# oldSHSDHDTD_system_1.net
KiCad netlist of a schematic drawn in EAGLE
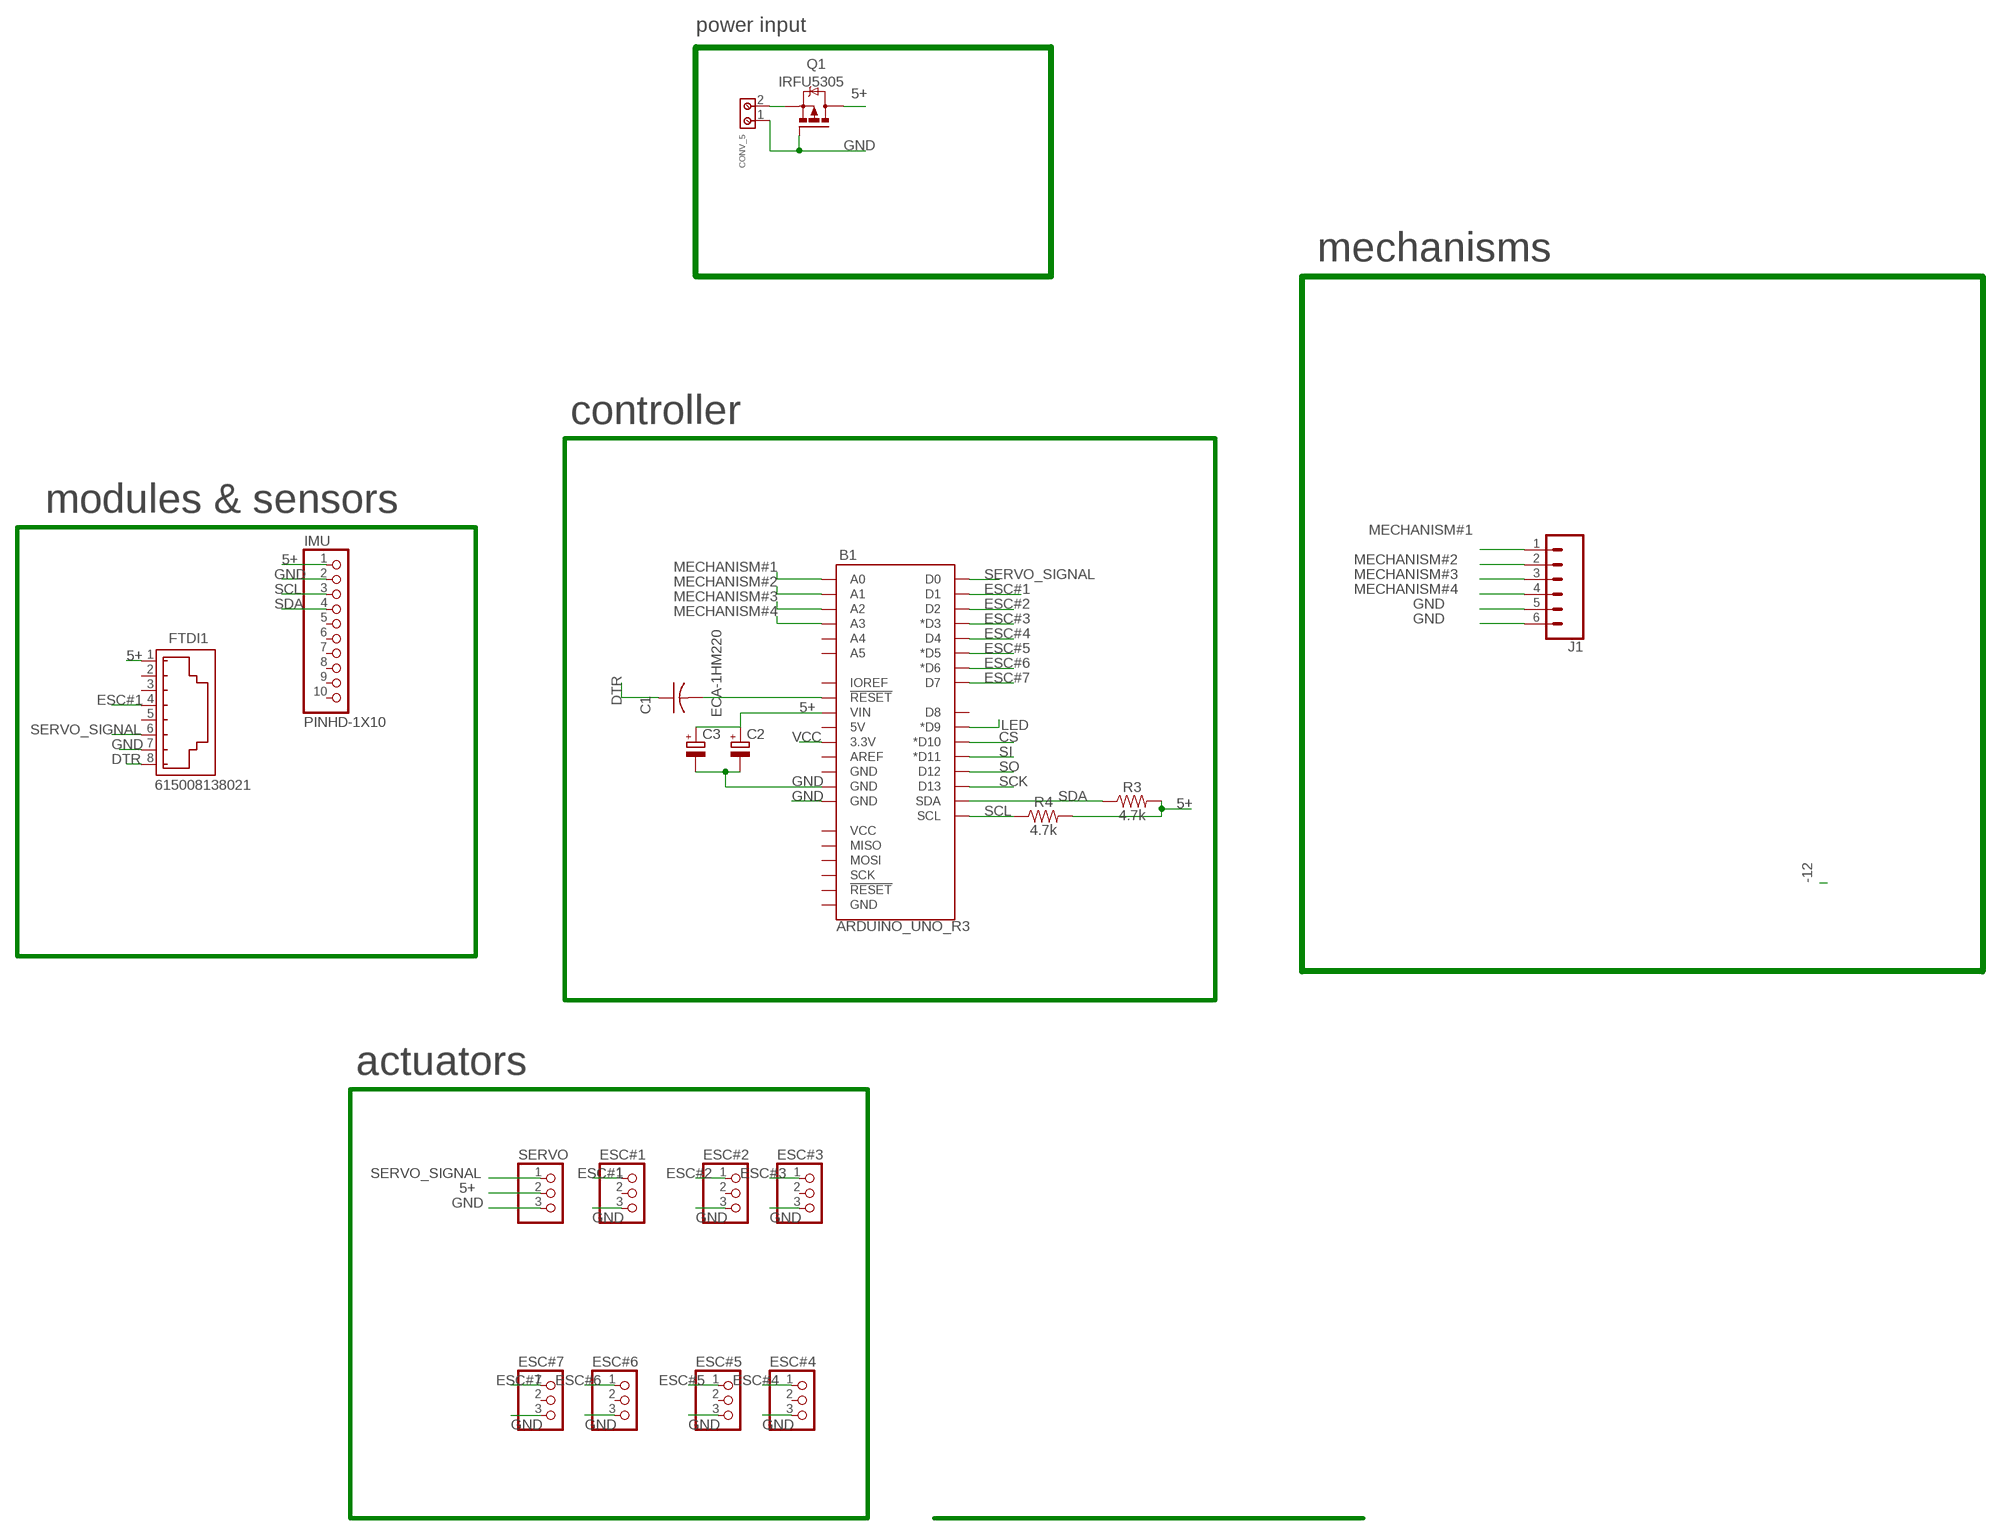
[diagram p0: schematic, sheet 1]

(export (version "E")
  (design (tool "Eeschema 10.0.6"))
  (components
    (comp (ref "B1")
      (value "ARDUINO_UNO_R3")
      (footprint "eagle-import:ARDUINO_R3")
      (libsource (lib "eagle-import") (part "ARDUINO_UNO_R3"))
    )
    (comp (ref "C1")
      (value "ECA-1HM220")
      (footprint "eagle-import:CAP_RADIAL_2MM")
      (fields
        (field (name "DIGIKEY_PART_NUMBER") "P5179-ND")
        (field (name "MANUFACTURER") "Panasonic Electronic Components")
        (field (name "CREATED_BY") "PCBLayout.com")
      )
      (libsource (lib "eagle-import") (part "ECA-1HM220"))
    )
    (comp (ref "C2")
      (value "CPOL-EUE7.5-16")
      (footprint "eagle-import:E7,5-16")
      (libsource (lib "eagle-import") (part "CPOL-EUE7.5-16"))
    )
    (comp (ref "C3")
      (value "CPOL-EUE7.5-16")
      (footprint "eagle-import:E7,5-16")
      (libsource (lib "eagle-import") (part "CPOL-EUE7.5-16"))
    )
    (comp (ref "CONV_5")
      (value "691213500002")
      (footprint "eagle-import:691213500002")
      (libsource (lib "eagle-import") (part "691213500002"))
    )
    (comp (ref "ESC#1")
      (value "PINHD-1X3")
      (footprint "eagle-import:1X03")
      (libsource (lib "eagle-import") (part "PINHD-1X3"))
    )
    (comp (ref "ESC#2")
      (value "PINHD-1X3")
      (footprint "eagle-import:1X03")
      (libsource (lib "eagle-import") (part "PINHD-1X3"))
    )
    (comp (ref "ESC#3")
      (value "PINHD-1X3")
      (footprint "eagle-import:1X03")
      (libsource (lib "eagle-import") (part "PINHD-1X3"))
    )
    (comp (ref "ESC#4")
      (value "PINHD-1X3")
      (footprint "eagle-import:1X03")
      (libsource (lib "eagle-import") (part "PINHD-1X3"))
    )
    (comp (ref "ESC#5")
      (value "PINHD-1X3")
      (footprint "eagle-import:1X03")
      (libsource (lib "eagle-import") (part "PINHD-1X3"))
    )
    (comp (ref "ESC#6")
      (value "PINHD-1X3")
      (footprint "eagle-import:1X03")
      (libsource (lib "eagle-import") (part "PINHD-1X3"))
    )
    (comp (ref "ESC#7")
      (value "PINHD-1X3")
      (footprint "eagle-import:1X03")
      (libsource (lib "eagle-import") (part "PINHD-1X3"))
    )
    (comp (ref "FTDI1")
      (value "615008138021")
      (footprint "eagle-import:615008138021")
      (libsource (lib "eagle-import") (part "615008138021"))
    )
    (comp (ref "IMU")
      (value "PINHD-1X10")
      (footprint "eagle-import:1X10-BIG")
      (libsource (lib "eagle-import") (part "PINHD-1X10"))
    )
    (comp (ref "J1")
      (value "CONN_06LOCK_LONGPADS")
      (footprint "eagle-import:1X06_LOCK_LONGPADS")
      (libsource (lib "eagle-import") (part "CONN_06LOCK_LONGPADS"))
    )
    (comp (ref "Q1")
      (value "IRFU5305")
      (footprint "eagle-import:I-PAK_TO251AA")
      (libsource (lib "eagle-import") (part "IRF?5305U"))
    )
    (comp (ref "R3")
      (value "4.7k")
      (footprint "eagle-import:AXIAL-0.3")
      (libsource (lib "eagle-import") (part "10MOHM-HORIZ-1/4W-5%"))
    )
    (comp (ref "R4")
      (value "4.7k")
      (footprint "eagle-import:AXIAL-0.3")
      (libsource (lib "eagle-import") (part "10MOHM-HORIZ-1/4W-5%"))
    )
    (comp (ref "SERVO")
      (value "PINHD-1X3")
      (footprint "eagle-import:1X03")
      (libsource (lib "eagle-import") (part "PINHD-1X3"))
    )
  )
  (nets
    (net (code "2") (name "/5+") (class "Default")
      (node (ref "B1") (pin "VIN") (pinfunction "VIN_VIN") (pintype "bidirectional"))
      (node (ref "C2") (pin "+") (pinfunction "+_+") (pintype "passive"))
      (node (ref "C3") (pin "+") (pinfunction "+_+") (pintype "passive"))
      (node (ref "FTDI1") (pin "1") (pinfunction "8_1") (pintype "passive"))
      (node (ref "IMU") (pin "1") (pinfunction "1_1") (pintype "passive"))
      (node (ref "Q1") (pin "2") (pinfunction "D_2") (pintype "passive"))
      (node (ref "R3") (pin "P$2") (pinfunction "2_P$2") (pintype "passive"))
      (node (ref "R4") (pin "P$2") (pinfunction "2_P$2") (pintype "passive"))
      (node (ref "SERVO") (pin "2") (pinfunction "2_2") (pintype "passive"))
    )
    (net (code "3") (name "/CS") (class "Default")
      (node (ref "B1") (pin "D10") (pinfunction "*D10_D10") (pintype "bidirectional"))
    )
    (net (code "4") (name "/DTR") (class "Default")
      (node (ref "C1") (pin "1") (pinfunction "1_1") (pintype "passive"))
      (node (ref "FTDI1") (pin "8") (pinfunction "1_8") (pintype "passive"))
    )
    (net (code "5") (name "/ESC#1") (class "Default")
      (node (ref "B1") (pin "D1") (pinfunction "D1_D1") (pintype "bidirectional"))
      (node (ref "ESC#1") (pin "1") (pinfunction "1_1") (pintype "passive"))
      (node (ref "FTDI1") (pin "4") (pinfunction "5_4") (pintype "passive"))
    )
    (net (code "6") (name "/ESC#2") (class "Default")
      (node (ref "B1") (pin "D2") (pinfunction "D2_D2") (pintype "bidirectional"))
      (node (ref "ESC#2") (pin "1") (pinfunction "1_1") (pintype "passive"))
    )
    (net (code "7") (name "/ESC#3") (class "Default")
      (node (ref "B1") (pin "D3") (pinfunction "*D3_D3") (pintype "bidirectional"))
      (node (ref "ESC#3") (pin "1") (pinfunction "1_1") (pintype "passive"))
    )
    (net (code "8") (name "/ESC#4") (class "Default")
      (node (ref "B1") (pin "D4") (pinfunction "D4_D4") (pintype "bidirectional"))
      (node (ref "ESC#4") (pin "1") (pinfunction "1_1") (pintype "passive"))
    )
    (net (code "9") (name "/ESC#5") (class "Default")
      (node (ref "B1") (pin "D5") (pinfunction "*D5_D5") (pintype "bidirectional"))
      (node (ref "ESC#5") (pin "1") (pinfunction "1_1") (pintype "passive"))
    )
    (net (code "10") (name "/ESC#6") (class "Default")
      (node (ref "B1") (pin "D6") (pinfunction "*D6_D6") (pintype "bidirectional"))
      (node (ref "ESC#6") (pin "1") (pinfunction "1_1") (pintype "passive"))
    )
    (net (code "11") (name "/ESC#7") (class "Default")
      (node (ref "B1") (pin "D7") (pinfunction "D7_D7") (pintype "bidirectional"))
      (node (ref "ESC#7") (pin "1") (pinfunction "1_1") (pintype "passive"))
    )
    (net (code "12") (name "/GND") (class "Default")
      (node (ref "B1") (pin "GND@2") (pinfunction "GND_GND@2") (pintype "bidirectional"))
      (node (ref "B1") (pin "GND@3") (pinfunction "GND_GND@3") (pintype "bidirectional"))
      (node (ref "C2") (pin "-") (pinfunction "-_-") (pintype "passive"))
      (node (ref "C3") (pin "-") (pinfunction "-_-") (pintype "passive"))
      (node (ref "CONV_5") (pin "1") (pinfunction "1_1") (pintype "passive"))
      (node (ref "ESC#1") (pin "3") (pinfunction "3_3") (pintype "passive"))
      (node (ref "ESC#2") (pin "3") (pinfunction "3_3") (pintype "passive"))
      (node (ref "ESC#3") (pin "3") (pinfunction "3_3") (pintype "passive"))
      (node (ref "ESC#4") (pin "3") (pinfunction "3_3") (pintype "passive"))
      (node (ref "ESC#5") (pin "3") (pinfunction "3_3") (pintype "passive"))
      (node (ref "ESC#6") (pin "3") (pinfunction "3_3") (pintype "passive"))
      (node (ref "ESC#7") (pin "3") (pinfunction "3_3") (pintype "passive"))
      (node (ref "FTDI1") (pin "7") (pinfunction "2_7") (pintype "passive"))
      (node (ref "IMU") (pin "2") (pinfunction "2_2") (pintype "passive"))
      (node (ref "J1") (pin "5") (pinfunction "5_5") (pintype "passive"))
      (node (ref "J1") (pin "6") (pinfunction "6_6") (pintype "passive"))
      (node (ref "Q1") (pin "1") (pinfunction "G_1") (pintype "passive"))
      (node (ref "SERVO") (pin "3") (pinfunction "3_3") (pintype "passive"))
    )
    (net (code "13") (name "/LED") (class "Default")
      (node (ref "B1") (pin "D9") (pinfunction "*D9_D9") (pintype "bidirectional"))
    )
    (net (code "14") (name "/MECHANISM#1") (class "Default")
      (node (ref "B1") (pin "A0") (pinfunction "A0_A0") (pintype "bidirectional"))
      (node (ref "J1") (pin "1") (pinfunction "1_1") (pintype "passive"))
    )
    (net (code "15") (name "/MECHANISM#2") (class "Default")
      (node (ref "B1") (pin "A1") (pinfunction "A1_A1") (pintype "bidirectional"))
      (node (ref "J1") (pin "2") (pinfunction "2_2") (pintype "passive"))
    )
    (net (code "16") (name "/MECHANISM#3") (class "Default")
      (node (ref "B1") (pin "A2") (pinfunction "A2_A2") (pintype "bidirectional"))
      (node (ref "J1") (pin "3") (pinfunction "3_3") (pintype "passive"))
    )
    (net (code "17") (name "/MECHANISM#4") (class "Default")
      (node (ref "B1") (pin "A3") (pinfunction "A3_A3") (pintype "bidirectional"))
      (node (ref "J1") (pin "4") (pinfunction "4_4") (pintype "passive"))
    )
    (net (code "19") (name "/SCK") (class "Default")
      (node (ref "B1") (pin "D13") (pinfunction "D13_D13") (pintype "bidirectional"))
    )
    (net (code "20") (name "/SCL") (class "Default")
      (node (ref "B1") (pin "SCL") (pinfunction "SCL_SCL") (pintype "bidirectional"))
      (node (ref "IMU") (pin "3") (pinfunction "3_3") (pintype "passive"))
      (node (ref "R4") (pin "P$1") (pinfunction "1_P$1") (pintype "passive"))
    )
    (net (code "21") (name "/SDA") (class "Default")
      (node (ref "B1") (pin "SDA") (pinfunction "SDA_SDA") (pintype "bidirectional"))
      (node (ref "IMU") (pin "4") (pinfunction "4_4") (pintype "passive"))
      (node (ref "R3") (pin "P$1") (pinfunction "1_P$1") (pintype "passive"))
    )
    (net (code "22") (name "/SERVO_SIGNAL") (class "Default")
      (node (ref "B1") (pin "D0") (pinfunction "D0_D0") (pintype "bidirectional"))
      (node (ref "FTDI1") (pin "6") (pinfunction "3_6") (pintype "passive"))
      (node (ref "SERVO") (pin "1") (pinfunction "1_1") (pintype "passive"))
    )
    (net (code "23") (name "/SI") (class "Default")
      (node (ref "B1") (pin "D11") (pinfunction "*D11_D11") (pintype "bidirectional"))
    )
    (net (code "24") (name "/SO") (class "Default")
      (node (ref "B1") (pin "D12") (pinfunction "D12_D12") (pintype "bidirectional"))
    )
    (net (code "25") (name "/VCC") (class "Default")
      (node (ref "B1") (pin "3.3V") (pinfunction "3.3V_3.3V") (pintype "bidirectional"))
    )
    (net (code "26") (name "Net-(B1-~{RESET}-PadRESET@1)") (class "Default")
      (node (ref "B1") (pin "RESET@1") (pinfunction "~{RESET}_RESET@1") (pintype "bidirectional"))
      (node (ref "C1") (pin "2") (pinfunction "2_2") (pintype "passive"))
    )
    (net (code "27") (name "Net-(Q1-S)") (class "Default")
      (node (ref "CONV_5") (pin "2") (pinfunction "2_2") (pintype "passive"))
      (node (ref "Q1") (pin "3") (pinfunction "S_3") (pintype "passive"))
    )
    (net (code "28") (name "unconnected-(B1-GND-PadGND@1)") (class "Default")
      (node (ref "B1") (pin "GND@1") (pinfunction "GND_GND@1") (pintype "bidirectional"))
    )
    (net (code "29") (name "unconnected-(B1-GND-PadGND@4)") (class "Default")
      (node (ref "B1") (pin "GND@4") (pinfunction "GND_GND@4") (pintype "bidirectional"))
    )
    (net (code "30") (name "unconnected-(B1-Pad5V)") (class "Default")
      (node (ref "B1") (pin "5V") (pinfunction "5V_5V") (pintype "bidirectional"))
    )
    (net (code "31") (name "unconnected-(B1-PadA4)") (class "Default")
      (node (ref "B1") (pin "A4") (pinfunction "A4_A4") (pintype "bidirectional"))
    )
    (net (code "32") (name "unconnected-(B1-PadA5)") (class "Default")
      (node (ref "B1") (pin "A5") (pinfunction "A5_A5") (pintype "bidirectional"))
    )
    (net (code "33") (name "unconnected-(B1-PadAREF)") (class "Default")
      (node (ref "B1") (pin "AREF") (pinfunction "AREF_AREF") (pintype "bidirectional"))
    )
    (net (code "34") (name "unconnected-(B1-PadD8)") (class "Default")
      (node (ref "B1") (pin "D8") (pinfunction "D8_D8") (pintype "bidirectional"))
    )
    (net (code "35") (name "unconnected-(B1-PadIOREF)") (class "Default")
      (node (ref "B1") (pin "IOREF") (pinfunction "IOREF_IOREF") (pintype "bidirectional"))
    )
    (net (code "36") (name "unconnected-(B1-PadMISO)") (class "Default")
      (node (ref "B1") (pin "MISO") (pinfunction "MISO_MISO") (pintype "bidirectional"))
    )
    (net (code "37") (name "unconnected-(B1-PadMOSI)") (class "Default")
      (node (ref "B1") (pin "MOSI") (pinfunction "MOSI_MOSI") (pintype "bidirectional"))
    )
    (net (code "38") (name "unconnected-(B1-PadSCK)") (class "Default")
      (node (ref "B1") (pin "SCK") (pinfunction "SCK_SCK") (pintype "bidirectional"))
    )
    (net (code "39") (name "unconnected-(B1-PadVCC)") (class "Default")
      (node (ref "B1") (pin "VCC") (pinfunction "VCC_VCC") (pintype "bidirectional"))
    )
    (net (code "40") (name "unconnected-(B1-~{RESET}-PadRESET@2)") (class "Default")
      (node (ref "B1") (pin "RESET@2") (pinfunction "~{RESET}_RESET@2") (pintype "bidirectional"))
    )
    (net (code "41") (name "unconnected-(ESC#1-Pad2)") (class "Default")
      (node (ref "ESC#1") (pin "2") (pinfunction "2_2") (pintype "passive"))
    )
    (net (code "42") (name "unconnected-(ESC#2-Pad2)") (class "Default")
      (node (ref "ESC#2") (pin "2") (pinfunction "2_2") (pintype "passive"))
    )
    (net (code "43") (name "unconnected-(ESC#3-Pad2)") (class "Default")
      (node (ref "ESC#3") (pin "2") (pinfunction "2_2") (pintype "passive"))
    )
    (net (code "44") (name "unconnected-(ESC#4-Pad2)") (class "Default")
      (node (ref "ESC#4") (pin "2") (pinfunction "2_2") (pintype "passive"))
    )
    (net (code "45") (name "unconnected-(ESC#5-Pad2)") (class "Default")
      (node (ref "ESC#5") (pin "2") (pinfunction "2_2") (pintype "passive"))
    )
    (net (code "46") (name "unconnected-(ESC#6-Pad2)") (class "Default")
      (node (ref "ESC#6") (pin "2") (pinfunction "2_2") (pintype "passive"))
    )
    (net (code "47") (name "unconnected-(ESC#7-Pad2)") (class "Default")
      (node (ref "ESC#7") (pin "2") (pinfunction "2_2") (pintype "passive"))
    )
    (net (code "48") (name "unconnected-(FTDI1-4-Pad5)") (class "Default")
      (node (ref "FTDI1") (pin "5") (pinfunction "4_5") (pintype "passive"))
    )
    (net (code "49") (name "unconnected-(FTDI1-6-Pad3)") (class "Default")
      (node (ref "FTDI1") (pin "3") (pinfunction "6_3") (pintype "passive"))
    )
    (net (code "50") (name "unconnected-(FTDI1-7-Pad2)") (class "Default")
      (node (ref "FTDI1") (pin "2") (pinfunction "7_2") (pintype "passive"))
    )
    (net (code "51") (name "unconnected-(IMU-Pad5)") (class "Default")
      (node (ref "IMU") (pin "5") (pinfunction "5_5") (pintype "passive"))
    )
    (net (code "52") (name "unconnected-(IMU-Pad6)") (class "Default")
      (node (ref "IMU") (pin "6") (pinfunction "6_6") (pintype "passive"))
    )
    (net (code "53") (name "unconnected-(IMU-Pad7)") (class "Default")
      (node (ref "IMU") (pin "7") (pinfunction "7_7") (pintype "passive"))
    )
    (net (code "54") (name "unconnected-(IMU-Pad8)") (class "Default")
      (node (ref "IMU") (pin "8") (pinfunction "8_8") (pintype "passive"))
    )
    (net (code "55") (name "unconnected-(IMU-Pad9)") (class "Default")
      (node (ref "IMU") (pin "9") (pinfunction "9_9") (pintype "passive"))
    )
    (net (code "56") (name "unconnected-(IMU-Pad10)") (class "Default")
      (node (ref "IMU") (pin "10") (pinfunction "10_10") (pintype "passive"))
    )
  )
)
